# DS3231.net
KiCad netlist of a schematic drawn in Altium Designer
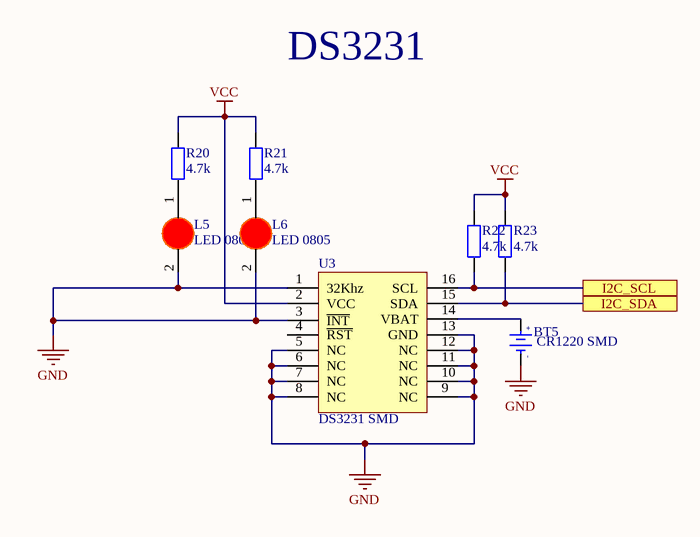
[diagram p0: DS3231.SchDoc]

(export (version "E")
  (design (tool "Eeschema 10.0.6"))
  (components
    (comp (ref "BT5")
      (value "CR1220 SMD")
      (footprint "DE PIN CR1220")
      (libsource (lib "Altium_Lib_by_KhueNguyenCreator") (part "De pin CR1220 SMD"))
    )
    (comp (ref "L5")
      (value "LED 0805")
      (footprint "LED-0805-Red")
      (description "Dán")
      (libsource (lib "Altium_Lib_by_KhueNguyenCreator") (part "LED 0805 Do"))
    )
    (comp (ref "L6")
      (value "LED 0805")
      (footprint "LED-0805-Red")
      (description "Dán")
      (libsource (lib "Altium_Lib_by_KhueNguyenCreator") (part "LED 0805 Do"))
    )
    (comp (ref "R20")
      (value "4.7k")
      (footprint "tro smd 0603")
      (description "Dán")
      (libsource (lib "Altium_Lib_by_KhueNguyenCreator") (part "Tro 0603 5% 4.7k"))
    )
    (comp (ref "R21")
      (value "4.7k")
      (footprint "tro smd 0603")
      (description "Dán")
      (libsource (lib "Altium_Lib_by_KhueNguyenCreator") (part "Tro 0603 5% 4.7k"))
    )
    (comp (ref "R22")
      (value "4.7k")
      (footprint "tro smd 0603")
      (description "Dán")
      (libsource (lib "Altium_Lib_by_KhueNguyenCreator") (part "Tro 0603 5% 4.7k"))
    )
    (comp (ref "R23")
      (value "4.7k")
      (footprint "tro smd 0603")
      (description "Dán")
      (libsource (lib "Altium_Lib_by_KhueNguyenCreator") (part "Tro 0603 5% 4.7k"))
    )
    (comp (ref "U3")
      (value "DS3231 SMD")
      (footprint "SOIC 16")
      (description "SOIC")
      (libsource (lib "Altium_Lib_by_KhueNguyenCreator") (part "DS3231 SMD"))
    )
  )
  (nets
    (net (code "1") (name "/I2C_SCL") (class "Default")
      (node (ref "R22") (pin "1") (pinfunction "1_1") (pintype "passive"))
      (node (ref "U3") (pin "16") (pinfunction "SCL_16") (pintype "power_in"))
    )
    (net (code "2") (name "/I2C_SDA") (class "Default")
      (node (ref "R23") (pin "1") (pinfunction "1_1") (pintype "passive"))
      (node (ref "U3") (pin "15") (pinfunction "SDA_15") (pintype "power_in"))
    )
    (net (code "3") (name "GND") (class "Default")
      (node (ref "BT5") (pin "2") (pinfunction "GND_2") (pintype "passive"))
      (node (ref "L5") (pin "2") (pinfunction "K_2") (pintype "passive"))
      (node (ref "L6") (pin "2") (pinfunction "K_2") (pintype "passive"))
      (node (ref "U3") (pin "1") (pinfunction "32Khz_1") (pintype "power_in"))
      (node (ref "U3") (pin "10") (pinfunction "NC_10") (pintype "power_in"))
      (node (ref "U3") (pin "11") (pinfunction "NC_11") (pintype "power_in"))
      (node (ref "U3") (pin "12") (pinfunction "NC_12") (pintype "power_in"))
      (node (ref "U3") (pin "13") (pinfunction "GND_13") (pintype "power_in"))
      (node (ref "U3") (pin "3") (pinfunction "~{INT}_3") (pintype "power_in"))
      (node (ref "U3") (pin "5") (pinfunction "NC_5") (pintype "power_in"))
      (node (ref "U3") (pin "6") (pinfunction "NC_6") (pintype "power_in"))
      (node (ref "U3") (pin "7") (pinfunction "NC_7") (pintype "power_in"))
      (node (ref "U3") (pin "8") (pinfunction "NC_8") (pintype "power_in"))
      (node (ref "U3") (pin "9") (pinfunction "NC_9") (pintype "power_in"))
    )
    (net (code "4") (name "Net-(BT5-+3V)") (class "Default")
      (node (ref "BT5") (pin "1") (pinfunction "+3V_1") (pintype "passive"))
      (node (ref "U3") (pin "14") (pinfunction "VBAT_14") (pintype "power_in"))
    )
    (net (code "5") (name "Net-(L5-A)") (class "Default")
      (node (ref "L5") (pin "1") (pinfunction "A_1") (pintype "passive"))
      (node (ref "R20") (pin "1") (pinfunction "1_1") (pintype "passive"))
    )
    (net (code "6") (name "Net-(L6-A)") (class "Default")
      (node (ref "L6") (pin "1") (pinfunction "A_1") (pintype "passive"))
      (node (ref "R21") (pin "1") (pinfunction "1_1") (pintype "passive"))
    )
    (net (code "7") (name "VCC") (class "Default")
      (node (ref "R20") (pin "2") (pinfunction "2_2") (pintype "passive"))
      (node (ref "R21") (pin "2") (pinfunction "2_2") (pintype "passive"))
      (node (ref "R22") (pin "2") (pinfunction "2_2") (pintype "passive"))
      (node (ref "R23") (pin "2") (pinfunction "2_2") (pintype "passive"))
      (node (ref "U3") (pin "2") (pinfunction "VCC_2") (pintype "power_in"))
    )
    (net (code "8") (name "unconnected-(U3-~{RST}-Pad4)") (class "Default")
      (node (ref "U3") (pin "4") (pinfunction "~{RST}_4") (pintype "power_in"))
    )
  )
)
